# ETHERNET.net
KiCad netlist of a schematic drawn in Altium Designer
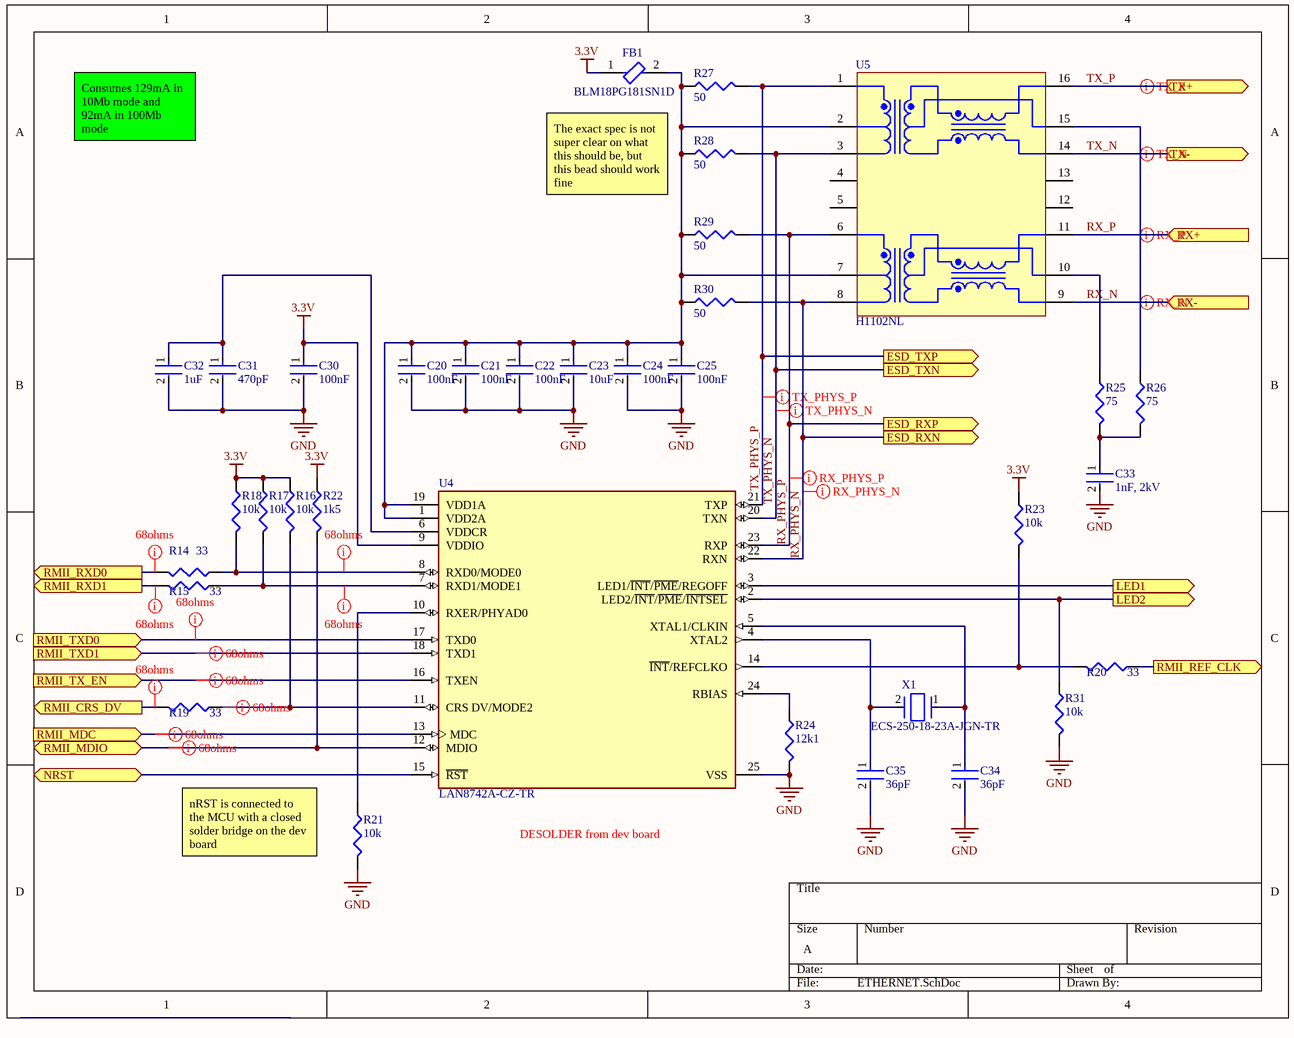
[diagram p0: ETHERNET.SchDoc]

(export (version "E")
  (design (tool "Eeschema 10.0.6"))
  (components
    (comp (ref "C20")
      (value "100nF")
      (footprint "FP-C0603C-CF-MFG")
      (description "Any 0603 Cap is fine here")
      (fields (field (name "TOLERANCE") "0.1") (field (name "MANUFACTURER") "KEMET"))
      (libsource (lib "Altium Content Vault") (part "b4654b650e69147ec39a6b967a45e02"))
    )
    (comp (ref "C21")
      (value "100nF")
      (footprint "FP-C0603C-CF-MFG")
      (description "Any 0603 Cap is fine here")
      (fields (field (name "TOLERANCE") "0.1") (field (name "MANUFACTURER") "KEMET"))
      (libsource (lib "Altium Content Vault") (part "b4654b650e69147ec39a6b967a45e02"))
    )
    (comp (ref "C22")
      (value "100nF")
      (footprint "FP-C0603C-CF-MFG")
      (description "Any 0603 Cap is fine here")
      (fields (field (name "TOLERANCE") "0.1") (field (name "MANUFACTURER") "KEMET"))
      (libsource (lib "Altium Content Vault") (part "b4654b650e69147ec39a6b967a45e02"))
    )
    (comp (ref "C23")
      (value "10uF")
      (footprint "FP-C0603C-CF-MFG")
      (description "Any 0603 Cap is fine here")
      (fields (field (name "TOLERANCE") "0.1") (field (name "MANUFACTURER") "KEMET"))
      (libsource (lib "Altium Content Vault") (part "b4654b650e69147ec39a6b967a45e02"))
    )
    (comp (ref "C24")
      (value "100nF")
      (footprint "FP-C0603C-CF-MFG")
      (description "Any 0603 Cap is fine here")
      (fields (field (name "TOLERANCE") "0.1") (field (name "MANUFACTURER") "KEMET"))
      (libsource (lib "Altium Content Vault") (part "b4654b650e69147ec39a6b967a45e02"))
    )
    (comp (ref "C25")
      (value "100nF")
      (footprint "FP-C0603C-CF-MFG")
      (description "Any 0603 Cap is fine here")
      (fields (field (name "TOLERANCE") "0.1") (field (name "MANUFACTURER") "KEMET"))
      (libsource (lib "Altium Content Vault") (part "b4654b650e69147ec39a6b967a45e02"))
    )
    (comp (ref "C30")
      (value "100nF")
      (footprint "FP-C0603C-CF-MFG")
      (description "Any 0603 Cap is fine here")
      (fields (field (name "TOLERANCE") "0.1") (field (name "MANUFACTURER") "KEMET"))
      (libsource (lib "Altium Content Vault") (part "b4654b650e69147ec39a6b967a45e02"))
    )
    (comp (ref "C31")
      (value "470pF")
      (footprint "FP-C0603C-CF-MFG")
      (description "Any 0603 Cap is fine here")
      (fields (field (name "TOLERANCE") "0.1") (field (name "MANUFACTURER") "KEMET"))
      (libsource (lib "Altium Content Vault") (part "b4654b650e69147ec39a6b967a45e02"))
    )
    (comp (ref "C32")
      (value "1uF")
      (footprint "FP-C0603C-CF-MFG")
      (description "Any 0603 Cap is fine here")
      (fields (field (name "TOLERANCE") "0.1") (field (name "MANUFACTURER") "KEMET"))
      (libsource (lib "Altium Content Vault") (part "b4654b650e69147ec39a6b967a45e02"))
    )
    (comp (ref "C33")
      (value "1nF, 2kV")
      (footprint "FP-C0603C-CF-MFG")
      (description "Any 0603 Cap is fine here")
      (fields (field (name "TOLERANCE") "0.1") (field (name "MANUFACTURER") "KEMET"))
      (libsource (lib "Altium Content Vault") (part "b4654b650e69147ec39a6b967a45e02"))
    )
    (comp (ref "C34")
      (value "36pF")
      (footprint "FP-C0603C-CF-MFG")
      (description "Any 0603 Cap is fine here")
      (fields (field (name "TOLERANCE") "0.1") (field (name "MANUFACTURER") "KEMET"))
      (libsource (lib "Altium Content Vault") (part "b4654b650e69147ec39a6b967a45e02"))
    )
    (comp (ref "C35")
      (value "36pF")
      (footprint "FP-C0603C-CF-MFG")
      (description "Any 0603 Cap is fine here")
      (fields (field (name "TOLERANCE") "0.1") (field (name "MANUFACTURER") "KEMET"))
      (libsource (lib "Altium Content Vault") (part "b4654b650e69147ec39a6b967a45e02"))
    )
    (comp (ref "FB1")
      (value "BLM18PG181SN1D")
      (footprint "FP-BLM18-0_15-t0_8-IPC_B")
      (description "Chip Ferrite Bead, 0603, 180Ω @ 100MHz, 0.09Ω, 25%, 1.5A")
      (fields (field (name "TOLERANCE") "25%"))
      (libsource (lib "Altium Content Vault") (part "5f30dd21d616792df468990f7003faa"))
    )
    (comp (ref "R14")
      (value "33")
      (footprint "J1-0603")
      (description "Resistor")
      (fields (field (name "PUBLISHER") "Altium Limited"))
      (libsource (lib "Miscellaneous Devices") (part "Res3"))
    )
    (comp (ref "R15")
      (value "33")
      (footprint "J1-0603")
      (description "Resistor")
      (fields (field (name "PUBLISHER") "Altium Limited"))
      (libsource (lib "Miscellaneous Devices") (part "Res3"))
    )
    (comp (ref "R16")
      (value "10k")
      (footprint "J1-0603")
      (description "Resistor")
      (fields (field (name "PUBLISHER") "Altium Limited"))
      (libsource (lib "Miscellaneous Devices") (part "Res3"))
    )
    (comp (ref "R17")
      (value "10k")
      (footprint "J1-0603")
      (description "Resistor")
      (fields (field (name "PUBLISHER") "Altium Limited"))
      (libsource (lib "Miscellaneous Devices") (part "Res3"))
    )
    (comp (ref "R18")
      (value "10k")
      (footprint "J1-0603")
      (description "Resistor")
      (fields (field (name "PUBLISHER") "Altium Limited"))
      (libsource (lib "Miscellaneous Devices") (part "Res3"))
    )
    (comp (ref "R19")
      (value "33")
      (footprint "J1-0603")
      (description "Resistor")
      (fields (field (name "PUBLISHER") "Altium Limited"))
      (libsource (lib "Miscellaneous Devices") (part "Res3"))
    )
    (comp (ref "R20")
      (value "33")
      (footprint "J1-0603")
      (description "Resistor")
      (fields (field (name "PUBLISHER") "Altium Limited"))
      (libsource (lib "Miscellaneous Devices") (part "Res3"))
    )
    (comp (ref "R21")
      (value "10k")
      (footprint "J1-0603")
      (description "Resistor")
      (fields (field (name "PUBLISHER") "Altium Limited"))
      (libsource (lib "Miscellaneous Devices") (part "Res3"))
    )
    (comp (ref "R22")
      (value "1k5")
      (footprint "J1-0603")
      (description "Resistor")
      (fields (field (name "PUBLISHER") "Altium Limited"))
      (libsource (lib "Miscellaneous Devices") (part "Res3"))
    )
    (comp (ref "R23")
      (value "10k")
      (footprint "J1-0603")
      (description "Resistor")
      (fields (field (name "PUBLISHER") "Altium Limited"))
      (libsource (lib "Miscellaneous Devices") (part "Res3"))
    )
    (comp (ref "R24")
      (value "12k1")
      (footprint "J1-0603")
      (description "Resistor")
      (fields (field (name "PUBLISHER") "Altium Limited"))
      (libsource (lib "Miscellaneous Devices") (part "Res3"))
    )
    (comp (ref "R25")
      (value "75")
      (footprint "J1-0603")
      (description "Resistor")
      (fields (field (name "PUBLISHER") "Altium Limited"))
      (libsource (lib "Miscellaneous Devices") (part "Res3"))
    )
    (comp (ref "R26")
      (value "75")
      (footprint "J1-0603")
      (description "Resistor")
      (fields (field (name "PUBLISHER") "Altium Limited"))
      (libsource (lib "Miscellaneous Devices") (part "Res3"))
    )
    (comp (ref "R27")
      (value "50")
      (footprint "J1-0603")
      (description "Resistor")
      (fields (field (name "PUBLISHER") "Altium Limited"))
      (libsource (lib "Miscellaneous Devices") (part "Res3"))
    )
    (comp (ref "R28")
      (value "50")
      (footprint "J1-0603")
      (description "Resistor")
      (fields (field (name "PUBLISHER") "Altium Limited"))
      (libsource (lib "Miscellaneous Devices") (part "Res3"))
    )
    (comp (ref "R29")
      (value "50")
      (footprint "J1-0603")
      (description "Resistor")
      (fields (field (name "PUBLISHER") "Altium Limited"))
      (libsource (lib "Miscellaneous Devices") (part "Res3"))
    )
    (comp (ref "R30")
      (value "50")
      (footprint "J1-0603")
      (description "Resistor")
      (fields (field (name "PUBLISHER") "Altium Limited"))
      (libsource (lib "Miscellaneous Devices") (part "Res3"))
    )
    (comp (ref "R31")
      (value "10k")
      (footprint "J1-0603")
      (description "Resistor")
      (fields (field (name "PUBLISHER") "Altium Limited"))
      (libsource (lib "Miscellaneous Devices") (part "Res3"))
    )
    (comp (ref "U4")
      (value "LAN8742A-CZ-TR")
      (footprint "FP-C04-143B-S4QFN-MFG")
      (description "IC TRANSCEIVER 1/1 24SQFN")
      (fields
        (field (name "MANUFACTURER") "Microchip")
        (field (name "OCTOPART") "https://octopart.com/lan8742a-cz-tr-microchip-29030587")
      )
      (libsource (lib "Altium Content Vault") (part "83151231c1ada07e85dcda6cce77793"))
    )
    (comp (ref "U5")
      (value "H1102NL")
      (footprint "PULS-MODULE-16_V")
      (fields (field (name "MANUFACTURER") "Pulse"))
      (libsource (lib "Altium Content Vault") (part "PULS-H1102NL-MODULE-16"))
    )
    (comp (ref "X1")
      (value "ECS-250-18-23A-JGN-TR")
      (footprint "FP-ECX-64A-MFG")
      (description "CRYSTAL 25.0000MHZ 18PF SMD")
      (libsource (lib "Altium Content Vault") (part "99724985039315a44fd0d1401b84e49"))
    )
  )
  (nets
    (net (code "1") (name "/LED1") (class "Default")
      (node (ref "U4") (pin "3") (pinfunction "LED1/~{INT}/~{PME}/REGOFF_3") (pintype "bidirectional"))
    )
    (net (code "2") (name "/LED2") (class "Default")
      (node (ref "R31") (pin "1") (pinfunction "1_1") (pintype "passive"))
      (node (ref "U4") (pin "2") (pinfunction "LED2/~{INT}/~{PME}/~{INTSEL}_2") (pintype "bidirectional"))
    )
    (net (code "3") (name "/NRST") (class "Default")
      (node (ref "U4") (pin "15") (pinfunction "~{RST}_15") (pintype "input"))
    )
    (net (code "4") (name "/RMII_CRS_DV") (class "Default")
      (node (ref "R19") (pin "2") (pinfunction "2_2") (pintype "passive"))
    )
    (net (code "5") (name "/RMII_MDC") (class "Default")
      (node (ref "U4") (pin "13") (pinfunction "MDC_13") (pintype "input"))
    )
    (net (code "6") (name "/RMII_MDIO") (class "Default")
      (node (ref "R22") (pin "2") (pinfunction "2_2") (pintype "passive"))
      (node (ref "U4") (pin "12") (pinfunction "MDIO_12") (pintype "bidirectional"))
    )
    (net (code "7") (name "/RMII_REF_CLK") (class "Default")
      (node (ref "R20") (pin "1") (pinfunction "1_1") (pintype "passive"))
    )
    (net (code "8") (name "/RMII_RXD0") (class "Default")
      (node (ref "R14") (pin "2") (pinfunction "2_2") (pintype "passive"))
    )
    (net (code "9") (name "/RMII_RXD1") (class "Default")
      (node (ref "R15") (pin "2") (pinfunction "2_2") (pintype "passive"))
    )
    (net (code "10") (name "/RMII_TXD0") (class "Default")
      (node (ref "U4") (pin "17") (pinfunction "TXD0_17") (pintype "input"))
    )
    (net (code "11") (name "/RMII_TXD1") (class "Default")
      (node (ref "U4") (pin "18") (pinfunction "TXD1_18") (pintype "input"))
    )
    (net (code "12") (name "/RMII_TX_EN") (class "Default")
      (node (ref "U4") (pin "16") (pinfunction "TXEN_16") (pintype "input"))
    )
    (net (code "13") (name "/RX_N") (class "Default")
      (node (ref "U5") (pin "9") (pinfunction "9_9") (pintype "passive"))
    )
    (net (code "14") (name "/RX_P") (class "Default")
      (node (ref "U5") (pin "11") (pinfunction "11_11") (pintype "passive"))
    )
    (net (code "15") (name "/RX_PHYS_N") (class "Default")
      (node (ref "R30") (pin "2") (pinfunction "2_2") (pintype "passive"))
      (node (ref "U4") (pin "22") (pinfunction "RXN_22") (pintype "bidirectional"))
      (node (ref "U5") (pin "8") (pinfunction "8_8") (pintype "passive"))
    )
    (net (code "16") (name "/RX_PHYS_P") (class "Default")
      (node (ref "R29") (pin "2") (pinfunction "2_2") (pintype "passive"))
      (node (ref "U4") (pin "23") (pinfunction "RXP_23") (pintype "bidirectional"))
      (node (ref "U5") (pin "6") (pinfunction "6_6") (pintype "passive"))
    )
    (net (code "17") (name "/TX_N") (class "Default")
      (node (ref "U5") (pin "14") (pinfunction "14_14") (pintype "passive"))
    )
    (net (code "18") (name "/TX_P") (class "Default")
      (node (ref "U5") (pin "16") (pinfunction "16_16") (pintype "passive"))
    )
    (net (code "19") (name "/TX_PHYS_N") (class "Default")
      (node (ref "R28") (pin "2") (pinfunction "2_2") (pintype "passive"))
      (node (ref "U4") (pin "20") (pinfunction "TXN_20") (pintype "bidirectional"))
      (node (ref "U5") (pin "3") (pinfunction "3_3") (pintype "passive"))
    )
    (net (code "20") (name "/TX_PHYS_P") (class "Default")
      (node (ref "R27") (pin "2") (pinfunction "2_2") (pintype "passive"))
      (node (ref "U4") (pin "21") (pinfunction "TXP_21") (pintype "bidirectional"))
      (node (ref "U5") (pin "1") (pinfunction "1_1") (pintype "passive"))
    )
    (net (code "21") (name "3.3V") (class "Default")
      (node (ref "C30") (pin "1") (pinfunction "1_1") (pintype "passive"))
      (node (ref "FB1") (pin "1") (pinfunction "1_1") (pintype "passive"))
      (node (ref "R16") (pin "1") (pinfunction "1_1") (pintype "passive"))
      (node (ref "R17") (pin "1") (pinfunction "1_1") (pintype "passive"))
      (node (ref "R18") (pin "1") (pinfunction "1_1") (pintype "passive"))
      (node (ref "R22") (pin "1") (pinfunction "1_1") (pintype "passive"))
      (node (ref "R23") (pin "1") (pinfunction "1_1") (pintype "passive"))
      (node (ref "U4") (pin "9") (pinfunction "VDDIO_9") (pintype "power_in"))
    )
    (net (code "22") (name "GND") (class "Default")
      (node (ref "C20") (pin "2") (pinfunction "2_2") (pintype "passive"))
      (node (ref "C21") (pin "2") (pinfunction "2_2") (pintype "passive"))
      (node (ref "C22") (pin "2") (pinfunction "2_2") (pintype "passive"))
      (node (ref "C23") (pin "2") (pinfunction "2_2") (pintype "passive"))
      (node (ref "C24") (pin "2") (pinfunction "2_2") (pintype "passive"))
      (node (ref "C25") (pin "2") (pinfunction "2_2") (pintype "passive"))
      (node (ref "C30") (pin "2") (pinfunction "2_2") (pintype "passive"))
      (node (ref "C31") (pin "2") (pinfunction "2_2") (pintype "passive"))
      (node (ref "C32") (pin "2") (pinfunction "2_2") (pintype "passive"))
      (node (ref "C33") (pin "2") (pinfunction "2_2") (pintype "passive"))
      (node (ref "C34") (pin "2") (pinfunction "2_2") (pintype "passive"))
      (node (ref "C35") (pin "2") (pinfunction "2_2") (pintype "passive"))
      (node (ref "R21") (pin "2") (pinfunction "2_2") (pintype "passive"))
      (node (ref "R24") (pin "2") (pinfunction "2_2") (pintype "passive"))
      (node (ref "R31") (pin "2") (pinfunction "2_2") (pintype "passive"))
      (node (ref "U4") (pin "25") (pinfunction "VSS_25") (pintype "power_in"))
    )
    (net (code "23") (name "Net-(C33-Pad1)") (class "Default")
      (node (ref "C33") (pin "1") (pinfunction "1_1") (pintype "passive"))
      (node (ref "R25") (pin "2") (pinfunction "2_2") (pintype "passive"))
      (node (ref "R26") (pin "2") (pinfunction "2_2") (pintype "passive"))
    )
    (net (code "24") (name "Net-(R25-Pad1)") (class "Default")
      (node (ref "R25") (pin "1") (pinfunction "1_1") (pintype "passive"))
      (node (ref "U5") (pin "10") (pinfunction "10_10") (pintype "passive"))
    )
    (net (code "25") (name "Net-(R26-Pad1)") (class "Default")
      (node (ref "R26") (pin "1") (pinfunction "1_1") (pintype "passive"))
      (node (ref "U5") (pin "15") (pinfunction "15_15") (pintype "passive"))
    )
    (net (code "26") (name "Net-(U4-CRS_DV{slash}MODE2)") (class "Default")
      (node (ref "R16") (pin "2") (pinfunction "2_2") (pintype "passive"))
      (node (ref "R19") (pin "1") (pinfunction "1_1") (pintype "passive"))
      (node (ref "U4") (pin "11") (pinfunction "CRS_DV/MODE2_11") (pintype "bidirectional"))
    )
    (net (code "27") (name "Net-(U4-RBIAS)") (class "Default")
      (node (ref "R24") (pin "1") (pinfunction "1_1") (pintype "passive"))
      (node (ref "U4") (pin "24") (pinfunction "RBIAS_24") (pintype "input"))
    )
    (net (code "28") (name "Net-(U4-RXD0{slash}MODE0)") (class "Default")
      (node (ref "R14") (pin "1") (pinfunction "1_1") (pintype "passive"))
      (node (ref "R18") (pin "2") (pinfunction "2_2") (pintype "passive"))
      (node (ref "U4") (pin "8") (pinfunction "RXD0/MODE0_8") (pintype "bidirectional"))
    )
    (net (code "29") (name "Net-(U4-RXD1{slash}MODE1)") (class "Default")
      (node (ref "R15") (pin "1") (pinfunction "1_1") (pintype "passive"))
      (node (ref "R17") (pin "2") (pinfunction "2_2") (pintype "passive"))
      (node (ref "U4") (pin "7") (pinfunction "RXD1/MODE1_7") (pintype "bidirectional"))
    )
    (net (code "30") (name "Net-(U4-RXER{slash}PHYAD0)") (class "Default")
      (node (ref "R21") (pin "1") (pinfunction "1_1") (pintype "passive"))
      (node (ref "U4") (pin "10") (pinfunction "RXER/PHYAD0_10") (pintype "bidirectional"))
    )
    (net (code "31") (name "Net-(U4-VDD1A)") (class "Default")
      (node (ref "C20") (pin "1") (pinfunction "1_1") (pintype "passive"))
      (node (ref "C21") (pin "1") (pinfunction "1_1") (pintype "passive"))
      (node (ref "C22") (pin "1") (pinfunction "1_1") (pintype "passive"))
      (node (ref "C23") (pin "1") (pinfunction "1_1") (pintype "passive"))
      (node (ref "C24") (pin "1") (pinfunction "1_1") (pintype "passive"))
      (node (ref "C25") (pin "1") (pinfunction "1_1") (pintype "passive"))
      (node (ref "FB1") (pin "2") (pinfunction "2_2") (pintype "passive"))
      (node (ref "R27") (pin "1") (pinfunction "1_1") (pintype "passive"))
      (node (ref "R28") (pin "1") (pinfunction "1_1") (pintype "passive"))
      (node (ref "R29") (pin "1") (pinfunction "1_1") (pintype "passive"))
      (node (ref "R30") (pin "1") (pinfunction "1_1") (pintype "passive"))
      (node (ref "U4") (pin "1") (pinfunction "VDD2A_1") (pintype "power_in"))
      (node (ref "U4") (pin "19") (pinfunction "VDD1A_19") (pintype "power_in"))
      (node (ref "U5") (pin "2") (pinfunction "2_2") (pintype "passive"))
      (node (ref "U5") (pin "7") (pinfunction "7_7") (pintype "passive"))
    )
    (net (code "32") (name "Net-(U4-VDDCR)") (class "Default")
      (node (ref "C31") (pin "1") (pinfunction "1_1") (pintype "passive"))
      (node (ref "C32") (pin "1") (pinfunction "1_1") (pintype "passive"))
      (node (ref "U4") (pin "6") (pinfunction "VDDCR_6") (pintype "power_in"))
    )
    (net (code "33") (name "Net-(U4-XTAL1{slash}CLKIN)") (class "Default")
      (node (ref "C34") (pin "1") (pinfunction "1_1") (pintype "passive"))
      (node (ref "U4") (pin "5") (pinfunction "XTAL1/CLKIN_5") (pintype "input"))
      (node (ref "X1") (pin "1") (pinfunction "In/Out_1") (pintype "passive"))
    )
    (net (code "34") (name "Net-(U4-XTAL2)") (class "Default")
      (node (ref "C35") (pin "1") (pinfunction "1_1") (pintype "passive"))
      (node (ref "U4") (pin "4") (pinfunction "XTAL2_4") (pintype "output"))
      (node (ref "X1") (pin "2") (pinfunction "Out/In_2") (pintype "passive"))
    )
    (net (code "35") (name "Net-(U4-~{INT}{slash}REFCLKO)") (class "Default")
      (node (ref "R20") (pin "2") (pinfunction "2_2") (pintype "passive"))
      (node (ref "R23") (pin "2") (pinfunction "2_2") (pintype "passive"))
      (node (ref "U4") (pin "14") (pinfunction "~{INT}/REFCLKO_14") (pintype "output"))
    )
    (net (code "36") (name "unconnected-(U5-Pad4)") (class "Default")
      (node (ref "U5") (pin "4") (pinfunction "4_4") (pintype "passive"))
    )
    (net (code "37") (name "unconnected-(U5-Pad5)") (class "Default")
      (node (ref "U5") (pin "5") (pinfunction "5_5") (pintype "passive"))
    )
    (net (code "38") (name "unconnected-(U5-Pad12)") (class "Default")
      (node (ref "U5") (pin "12") (pinfunction "12_12") (pintype "passive"))
    )
    (net (code "39") (name "unconnected-(U5-Pad13)") (class "Default")
      (node (ref "U5") (pin "13") (pinfunction "13_13") (pintype "passive"))
    )
  )
)
